# FLIP_FLOP_4_LED.net
KiCad netlist of a schematic drawn in EAGLE
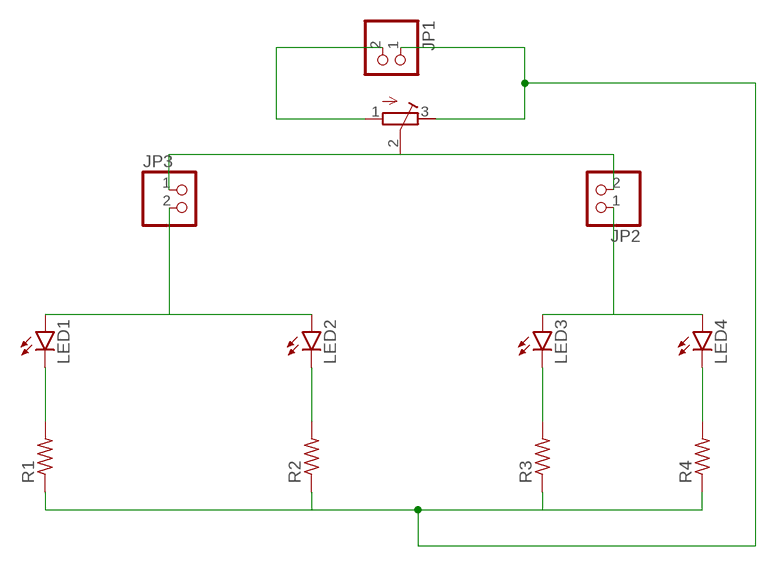
[diagram p0: schematic, sheet 1]

(export (version "E")
  (design (tool "Eeschema 10.0.6"))
  (components
    (comp (ref "JP1")
      (value "PINHD-1X2")
      (footprint "eagle-import:1X02")
      (libsource (lib "eagle-import") (part "PINHD-1X2"))
    )
    (comp (ref "JP2")
      (value "PINHD-1X2")
      (footprint "eagle-import:1X02")
      (libsource (lib "eagle-import") (part "PINHD-1X2"))
    )
    (comp (ref "JP3")
      (value "PINHD-1X2")
      (footprint "eagle-import:1X02")
      (libsource (lib "eagle-import") (part "PINHD-1X2"))
    )
    (comp (ref "LED1")
      (value "TLLG4400")
      (footprint "eagle-import:LED3MM")
      (fields (field (name "MF") "VISHAY SEMICONDUCTOR"))
      (libsource (lib "eagle-import") (part "TLLG4400"))
    )
    (comp (ref "LED2")
      (value "TLLG4400")
      (footprint "eagle-import:LED3MM")
      (fields (field (name "MF") "VISHAY SEMICONDUCTOR"))
      (libsource (lib "eagle-import") (part "TLLG4400"))
    )
    (comp (ref "LED3")
      (value "TLLR4400")
      (footprint "eagle-import:LED3MM")
      (fields (field (name "MF") "VISHAY SEMICONDUCTOR"))
      (libsource (lib "eagle-import") (part "TLLR4400"))
    )
    (comp (ref "LED4")
      (value "TLLR4400")
      (footprint "eagle-import:LED3MM")
      (fields (field (name "MF") "VISHAY SEMICONDUCTOR"))
      (libsource (lib "eagle-import") (part "TLLR4400"))
    )
    (comp (ref "R1")
      (value "R-US_0204/7")
      (footprint "eagle-import:0204_7")
      (libsource (lib "eagle-import") (part "R-US_0204/7"))
    )
    (comp (ref "R2")
      (value "R-US_0204/7")
      (footprint "eagle-import:0204_7")
      (libsource (lib "eagle-import") (part "R-US_0204/7"))
    )
    (comp (ref "R3")
      (value "R-US_0204/7")
      (footprint "eagle-import:0204_7")
      (libsource (lib "eagle-import") (part "R-US_0204/7"))
    )
    (comp (ref "R4")
      (value "R-US_0204/7")
      (footprint "eagle-import:0204_7")
      (libsource (lib "eagle-import") (part "R-US_0204/7"))
    )
    (comp (ref "R5")
      (value "R-TRIMM3339P")
      (footprint "eagle-import:RTRIM3339P")
      (libsource (lib "eagle-import") (part "R-TRIMM3339P"))
    )
  )
  (nets
    (net (code "1") (name "Net-(JP2-Pad1)") (class "Default")
      (node (ref "JP2") (pin "1") (pinfunction "1_1") (pintype "passive"))
      (node (ref "LED3") (pin "A") (pinfunction "A_A") (pintype "passive"))
      (node (ref "LED4") (pin "A") (pinfunction "A_A") (pintype "passive"))
    )
    (net (code "2") (name "Net-(JP3-Pad2)") (class "Default")
      (node (ref "JP3") (pin "2") (pinfunction "2_2") (pintype "passive"))
      (node (ref "LED1") (pin "A") (pinfunction "A_A") (pintype "passive"))
      (node (ref "LED2") (pin "A") (pinfunction "A_A") (pintype "passive"))
    )
    (net (code "3") (name "Net-(LED1-C)") (class "Default")
      (node (ref "LED1") (pin "K") (pinfunction "C_K") (pintype "passive"))
      (node (ref "R1") (pin "2") (pinfunction "2_2") (pintype "passive"))
    )
    (net (code "4") (name "Net-(LED2-C)") (class "Default")
      (node (ref "LED2") (pin "K") (pinfunction "C_K") (pintype "passive"))
      (node (ref "R2") (pin "2") (pinfunction "2_2") (pintype "passive"))
    )
    (net (code "5") (name "Net-(LED3-C)") (class "Default")
      (node (ref "LED3") (pin "K") (pinfunction "C_K") (pintype "passive"))
      (node (ref "R3") (pin "2") (pinfunction "2_2") (pintype "passive"))
    )
    (net (code "6") (name "Net-(LED4-C)") (class "Default")
      (node (ref "LED4") (pin "K") (pinfunction "C_K") (pintype "passive"))
      (node (ref "R4") (pin "2") (pinfunction "2_2") (pintype "passive"))
    )
    (net (code "7") (name "Net-(R5-A)") (class "Default")
      (node (ref "JP1") (pin "2") (pinfunction "2_2") (pintype "passive"))
      (node (ref "R5") (pin "1") (pinfunction "A_1") (pintype "passive"))
    )
    (net (code "8") (name "Net-(R5-E)") (class "Default")
      (node (ref "JP1") (pin "1") (pinfunction "1_1") (pintype "passive"))
      (node (ref "R1") (pin "1") (pinfunction "1_1") (pintype "passive"))
      (node (ref "R2") (pin "1") (pinfunction "1_1") (pintype "passive"))
      (node (ref "R3") (pin "1") (pinfunction "1_1") (pintype "passive"))
      (node (ref "R4") (pin "1") (pinfunction "1_1") (pintype "passive"))
      (node (ref "R5") (pin "3") (pinfunction "E_3") (pintype "passive"))
    )
    (net (code "9") (name "Net-(R5-S)") (class "Default")
      (node (ref "JP2") (pin "2") (pinfunction "2_2") (pintype "passive"))
      (node (ref "JP3") (pin "1") (pinfunction "1_1") (pintype "passive"))
      (node (ref "R5") (pin "2") (pinfunction "S_2") (pintype "passive"))
    )
  )
)
